# ENCF.net
KiCad netlist of a schematic drawn in EAGLE
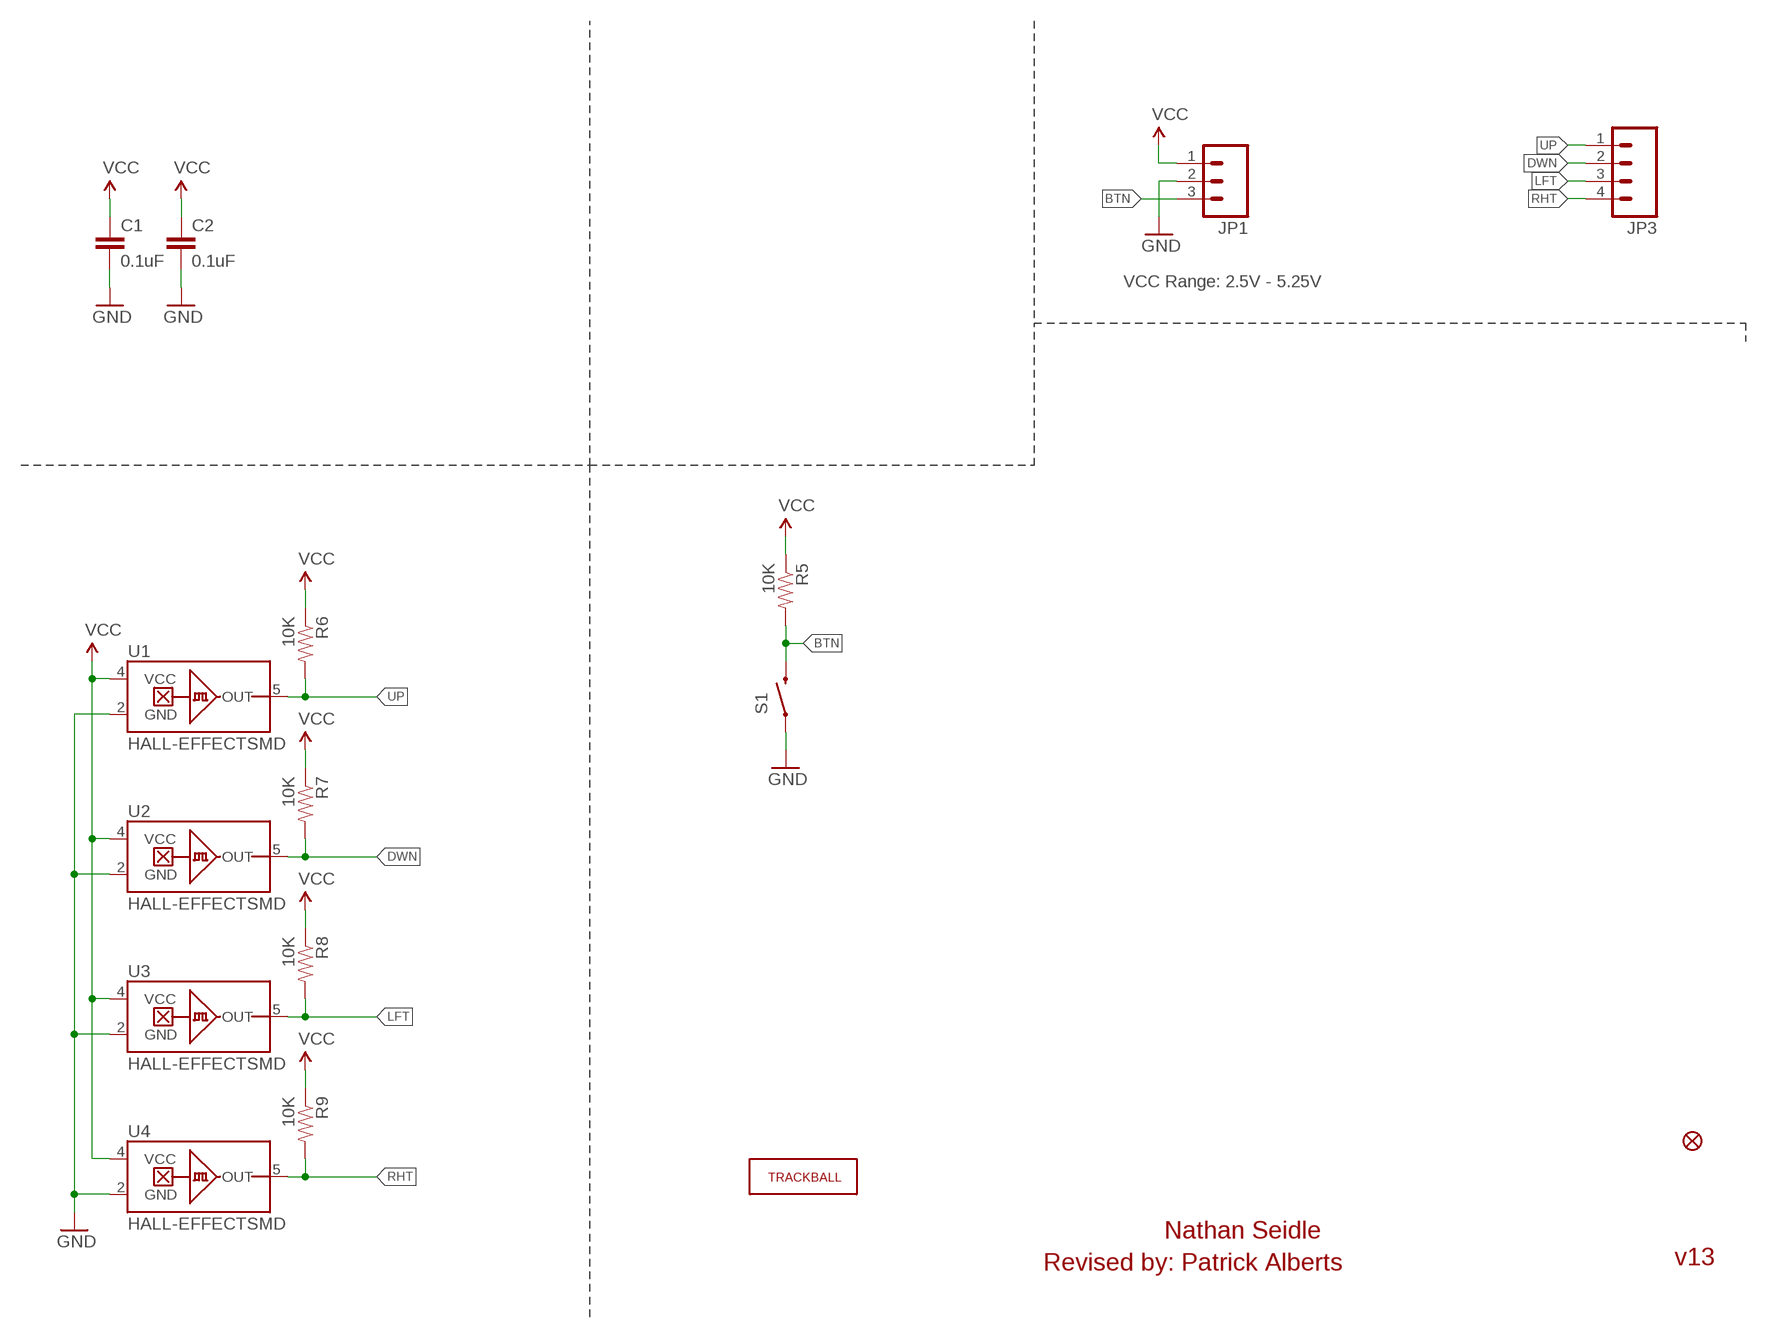
[diagram p0: schematic, sheet 1]

(export (version "E")
  (design (tool "Eeschema 10.0.6"))
  (components
    (comp (ref "C1")
      (value "0.1uF")
      (footprint "eagle-import:0603-CAP")
      (libsource (lib "eagle-import") (part "0.1UF-25V(+80/-20%)(0603)"))
    )
    (comp (ref "C2")
      (value "0.1uF")
      (footprint "eagle-import:0603-CAP")
      (libsource (lib "eagle-import") (part "0.1UF-25V(+80/-20%)(0603)"))
    )
    (comp (ref "E$2")
      (value "FIDUCIAL1X2")
      (footprint "eagle-import:FIDUCIAL-1X2")
      (libsource (lib "eagle-import") (part "FIDUCIAL1X2"))
    )
    (comp (ref "JP1")
      (value "M03PTH")
      (footprint "eagle-import:1X03")
      (libsource (lib "eagle-import") (part "M03PTH"))
    )
    (comp (ref "JP3")
      (value "M04PTH")
      (footprint "eagle-import:1X04")
      (libsource (lib "eagle-import") (part "M04PTH"))
    )
    (comp (ref "R5")
      (value "10K")
      (footprint "eagle-import:0603-RES")
      (libsource (lib "eagle-import") (part "10KOHM1/10W1%(0603)0603"))
    )
    (comp (ref "R6")
      (value "10K")
      (footprint "eagle-import:0603-RES")
      (libsource (lib "eagle-import") (part "10KOHM1/10W1%(0603)0603"))
    )
    (comp (ref "R7")
      (value "10K")
      (footprint "eagle-import:0603-RES")
      (libsource (lib "eagle-import") (part "10KOHM1/10W1%(0603)0603"))
    )
    (comp (ref "R8")
      (value "10K")
      (footprint "eagle-import:0603-RES")
      (libsource (lib "eagle-import") (part "10KOHM1/10W1%(0603)0603"))
    )
    (comp (ref "R9")
      (value "10K")
      (footprint "eagle-import:0603-RES")
      (libsource (lib "eagle-import") (part "10KOHM1/10W1%(0603)0603"))
    )
    (comp (ref "S1")
      (value "SWITCH-MOMENTARY-2SMD-2")
      (footprint "eagle-import:TACTILE_SWITCH_SMD-2")
      (libsource (lib "eagle-import") (part "SWITCH-MOMENTARY-2SMD-2"))
    )
    (comp (ref "U$3")
      (value "TRACKBALLMECH")
      (footprint "eagle-import:TRACKBALL")
      (libsource (lib "eagle-import") (part "TRACKBALLMECH"))
    )
    (comp (ref "U1")
      (value "HALL-EFFECTSMD")
      (footprint "eagle-import:SC70")
      (libsource (lib "eagle-import") (part "HALL-EFFECTSMD"))
    )
    (comp (ref "U2")
      (value "HALL-EFFECTSMD")
      (footprint "eagle-import:SC70")
      (libsource (lib "eagle-import") (part "HALL-EFFECTSMD"))
    )
    (comp (ref "U3")
      (value "HALL-EFFECTSMD")
      (footprint "eagle-import:SC70")
      (libsource (lib "eagle-import") (part "HALL-EFFECTSMD"))
    )
    (comp (ref "U4")
      (value "HALL-EFFECTSMD")
      (footprint "eagle-import:SC70")
      (libsource (lib "eagle-import") (part "HALL-EFFECTSMD"))
    )
  )
  (nets
    (net (code "1") (name "BTN") (class "Default")
      (node (ref "JP1") (pin "3") (pinfunction "3_3") (pintype "passive"))
      (node (ref "R5") (pin "2") (pinfunction "2_2") (pintype "passive"))
      (node (ref "S1") (pin "1") (pinfunction "2_1") (pintype "passive"))
    )
    (net (code "2") (name "DWN") (class "Default")
      (node (ref "JP3") (pin "2") (pinfunction "2_2") (pintype "passive"))
      (node (ref "R7") (pin "2") (pinfunction "2_2") (pintype "passive"))
      (node (ref "U2") (pin "5") (pinfunction "OUT_5") (pintype "bidirectional"))
    )
    (net (code "3") (name "GND") (class "Default")
      (node (ref "C1") (pin "2") (pinfunction "2_2") (pintype "passive"))
      (node (ref "C2") (pin "2") (pinfunction "2_2") (pintype "passive"))
      (node (ref "JP1") (pin "2") (pinfunction "2_2") (pintype "passive"))
      (node (ref "S1") (pin "2") (pinfunction "1_2") (pintype "passive"))
      (node (ref "U1") (pin "2") (pinfunction "GND_2") (pintype "bidirectional"))
      (node (ref "U2") (pin "2") (pinfunction "GND_2") (pintype "bidirectional"))
      (node (ref "U3") (pin "2") (pinfunction "GND_2") (pintype "bidirectional"))
      (node (ref "U4") (pin "2") (pinfunction "GND_2") (pintype "bidirectional"))
    )
    (net (code "4") (name "LFT") (class "Default")
      (node (ref "JP3") (pin "3") (pinfunction "3_3") (pintype "passive"))
      (node (ref "R8") (pin "2") (pinfunction "2_2") (pintype "passive"))
      (node (ref "U3") (pin "5") (pinfunction "OUT_5") (pintype "bidirectional"))
    )
    (net (code "5") (name "RHT") (class "Default")
      (node (ref "JP3") (pin "4") (pinfunction "4_4") (pintype "passive"))
      (node (ref "R9") (pin "2") (pinfunction "2_2") (pintype "passive"))
      (node (ref "U4") (pin "5") (pinfunction "OUT_5") (pintype "bidirectional"))
    )
    (net (code "6") (name "UP") (class "Default")
      (node (ref "JP3") (pin "1") (pinfunction "1_1") (pintype "passive"))
      (node (ref "R6") (pin "2") (pinfunction "2_2") (pintype "passive"))
      (node (ref "U1") (pin "5") (pinfunction "OUT_5") (pintype "bidirectional"))
    )
    (net (code "7") (name "VCC") (class "Default")
      (node (ref "C1") (pin "1") (pinfunction "1_1") (pintype "passive"))
      (node (ref "C2") (pin "1") (pinfunction "1_1") (pintype "passive"))
      (node (ref "JP1") (pin "1") (pinfunction "1_1") (pintype "passive"))
      (node (ref "R5") (pin "1") (pinfunction "1_1") (pintype "passive"))
      (node (ref "R6") (pin "1") (pinfunction "1_1") (pintype "passive"))
      (node (ref "R7") (pin "1") (pinfunction "1_1") (pintype "passive"))
      (node (ref "R8") (pin "1") (pinfunction "1_1") (pintype "passive"))
      (node (ref "R9") (pin "1") (pinfunction "1_1") (pintype "passive"))
      (node (ref "U1") (pin "4") (pinfunction "VCC_4") (pintype "bidirectional"))
      (node (ref "U2") (pin "4") (pinfunction "VCC_4") (pintype "bidirectional"))
      (node (ref "U3") (pin "4") (pinfunction "VCC_4") (pintype "bidirectional"))
      (node (ref "U4") (pin "4") (pinfunction "VCC_4") (pintype "bidirectional"))
    )
  )
)
